# Output_Connectors.net
KiCad netlist of a schematic drawn in Altium Designer
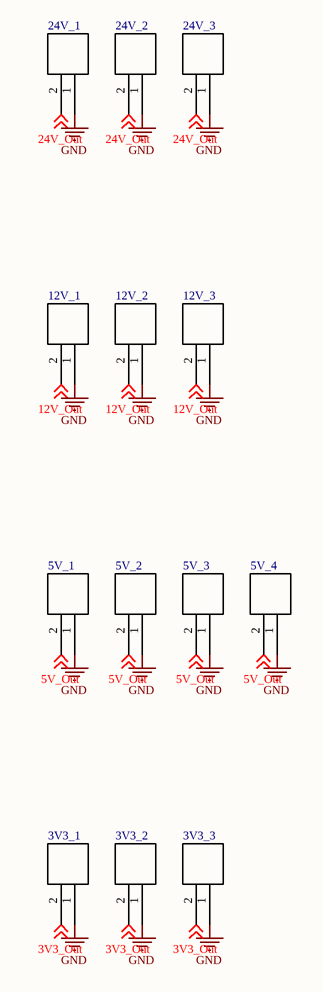
[diagram p0: Output Connectors.SchDoc]

(export (version "E")
  (design (tool "Eeschema 10.0.6"))
  (components
    (comp (ref "3V3_1")
      (value "Molex 6.5MM  power connector")
      (footprint "power connector")
      (libsource (lib "Husky Robotics Standard Library 2019-2020") (part "Molex 6.5MM  power connector"))
    )
    (comp (ref "3V3_2")
      (value "Molex 6.5MM  power connector")
      (footprint "power connector")
      (libsource (lib "Husky Robotics Standard Library 2019-2020") (part "Molex 6.5MM  power connector"))
    )
    (comp (ref "3V3_3")
      (value "Molex 6.5MM  power connector")
      (footprint "power connector")
      (libsource (lib "Husky Robotics Standard Library 2019-2020") (part "Molex 6.5MM  power connector"))
    )
    (comp (ref "5V_1")
      (value "Molex 6.5MM  power connector")
      (footprint "power connector")
      (libsource (lib "Husky Robotics Standard Library 2019-2020") (part "Molex 6.5MM  power connector"))
    )
    (comp (ref "5V_2")
      (value "Molex 6.5MM  power connector")
      (footprint "power connector")
      (libsource (lib "Husky Robotics Standard Library 2019-2020") (part "Molex 6.5MM  power connector"))
    )
    (comp (ref "5V_3")
      (value "Molex 6.5MM  power connector")
      (footprint "power connector")
      (libsource (lib "Husky Robotics Standard Library 2019-2020") (part "Molex 6.5MM  power connector"))
    )
    (comp (ref "5V_4")
      (value "Molex 6.5MM  power connector")
      (footprint "power connector")
      (libsource (lib "Husky Robotics Standard Library 2019-2020") (part "Molex 6.5MM  power connector"))
    )
    (comp (ref "12V_1")
      (value "Molex 6.5MM  power connector")
      (footprint "power connector")
      (libsource (lib "Husky Robotics Standard Library 2019-2020") (part "Molex 6.5MM  power connector"))
    )
    (comp (ref "12V_2")
      (value "Molex 6.5MM  power connector")
      (footprint "power connector")
      (libsource (lib "Husky Robotics Standard Library 2019-2020") (part "Molex 6.5MM  power connector"))
    )
    (comp (ref "12V_3")
      (value "Molex 6.5MM  power connector")
      (footprint "power connector")
      (libsource (lib "Husky Robotics Standard Library 2019-2020") (part "Molex 6.5MM  power connector"))
    )
    (comp (ref "24V_1")
      (value "Molex 6.5MM  power connector")
      (footprint "power connector")
      (libsource (lib "Husky Robotics Standard Library 2019-2020") (part "Molex 6.5MM  power connector"))
    )
    (comp (ref "24V_2")
      (value "Molex 6.5MM  power connector")
      (footprint "power connector")
      (libsource (lib "Husky Robotics Standard Library 2019-2020") (part "Molex 6.5MM  power connector"))
    )
    (comp (ref "24V_3")
      (value "Molex 6.5MM  power connector")
      (footprint "power connector")
      (libsource (lib "Husky Robotics Standard Library 2019-2020") (part "Molex 6.5MM  power connector"))
    )
  )
  (nets
    (net (code "1") (name "3V3_Out") (class "Default")
      (node (ref "3V3_1") (pin "2") (pintype "passive"))
      (node (ref "3V3_2") (pin "2") (pintype "passive"))
      (node (ref "3V3_3") (pin "2") (pintype "passive"))
    )
    (net (code "2") (name "5V_Out") (class "Default")
      (node (ref "5V_1") (pin "2") (pintype "passive"))
      (node (ref "5V_2") (pin "2") (pintype "passive"))
      (node (ref "5V_3") (pin "2") (pintype "passive"))
      (node (ref "5V_4") (pin "2") (pintype "passive"))
    )
    (net (code "3") (name "12V_Out") (class "Default")
      (node (ref "12V_1") (pin "2") (pintype "passive"))
      (node (ref "12V_2") (pin "2") (pintype "passive"))
      (node (ref "12V_3") (pin "2") (pintype "passive"))
    )
    (net (code "4") (name "24V_Out") (class "Default")
      (node (ref "24V_1") (pin "2") (pintype "passive"))
      (node (ref "24V_2") (pin "2") (pintype "passive"))
      (node (ref "24V_3") (pin "2") (pintype "passive"))
    )
    (net (code "5") (name "GND") (class "Default")
      (node (ref "12V_1") (pin "1") (pintype "passive"))
      (node (ref "12V_2") (pin "1") (pintype "passive"))
      (node (ref "12V_3") (pin "1") (pintype "passive"))
      (node (ref "24V_1") (pin "1") (pintype "passive"))
      (node (ref "24V_2") (pin "1") (pintype "passive"))
      (node (ref "24V_3") (pin "1") (pintype "passive"))
      (node (ref "3V3_1") (pin "1") (pintype "passive"))
      (node (ref "3V3_2") (pin "1") (pintype "passive"))
      (node (ref "3V3_3") (pin "1") (pintype "passive"))
      (node (ref "5V_1") (pin "1") (pintype "passive"))
      (node (ref "5V_2") (pin "1") (pintype "passive"))
      (node (ref "5V_3") (pin "1") (pintype "passive"))
      (node (ref "5V_4") (pin "1") (pintype "passive"))
    )
  )
)
